# V2.net
KiCad netlist of a schematic drawn in EAGLE
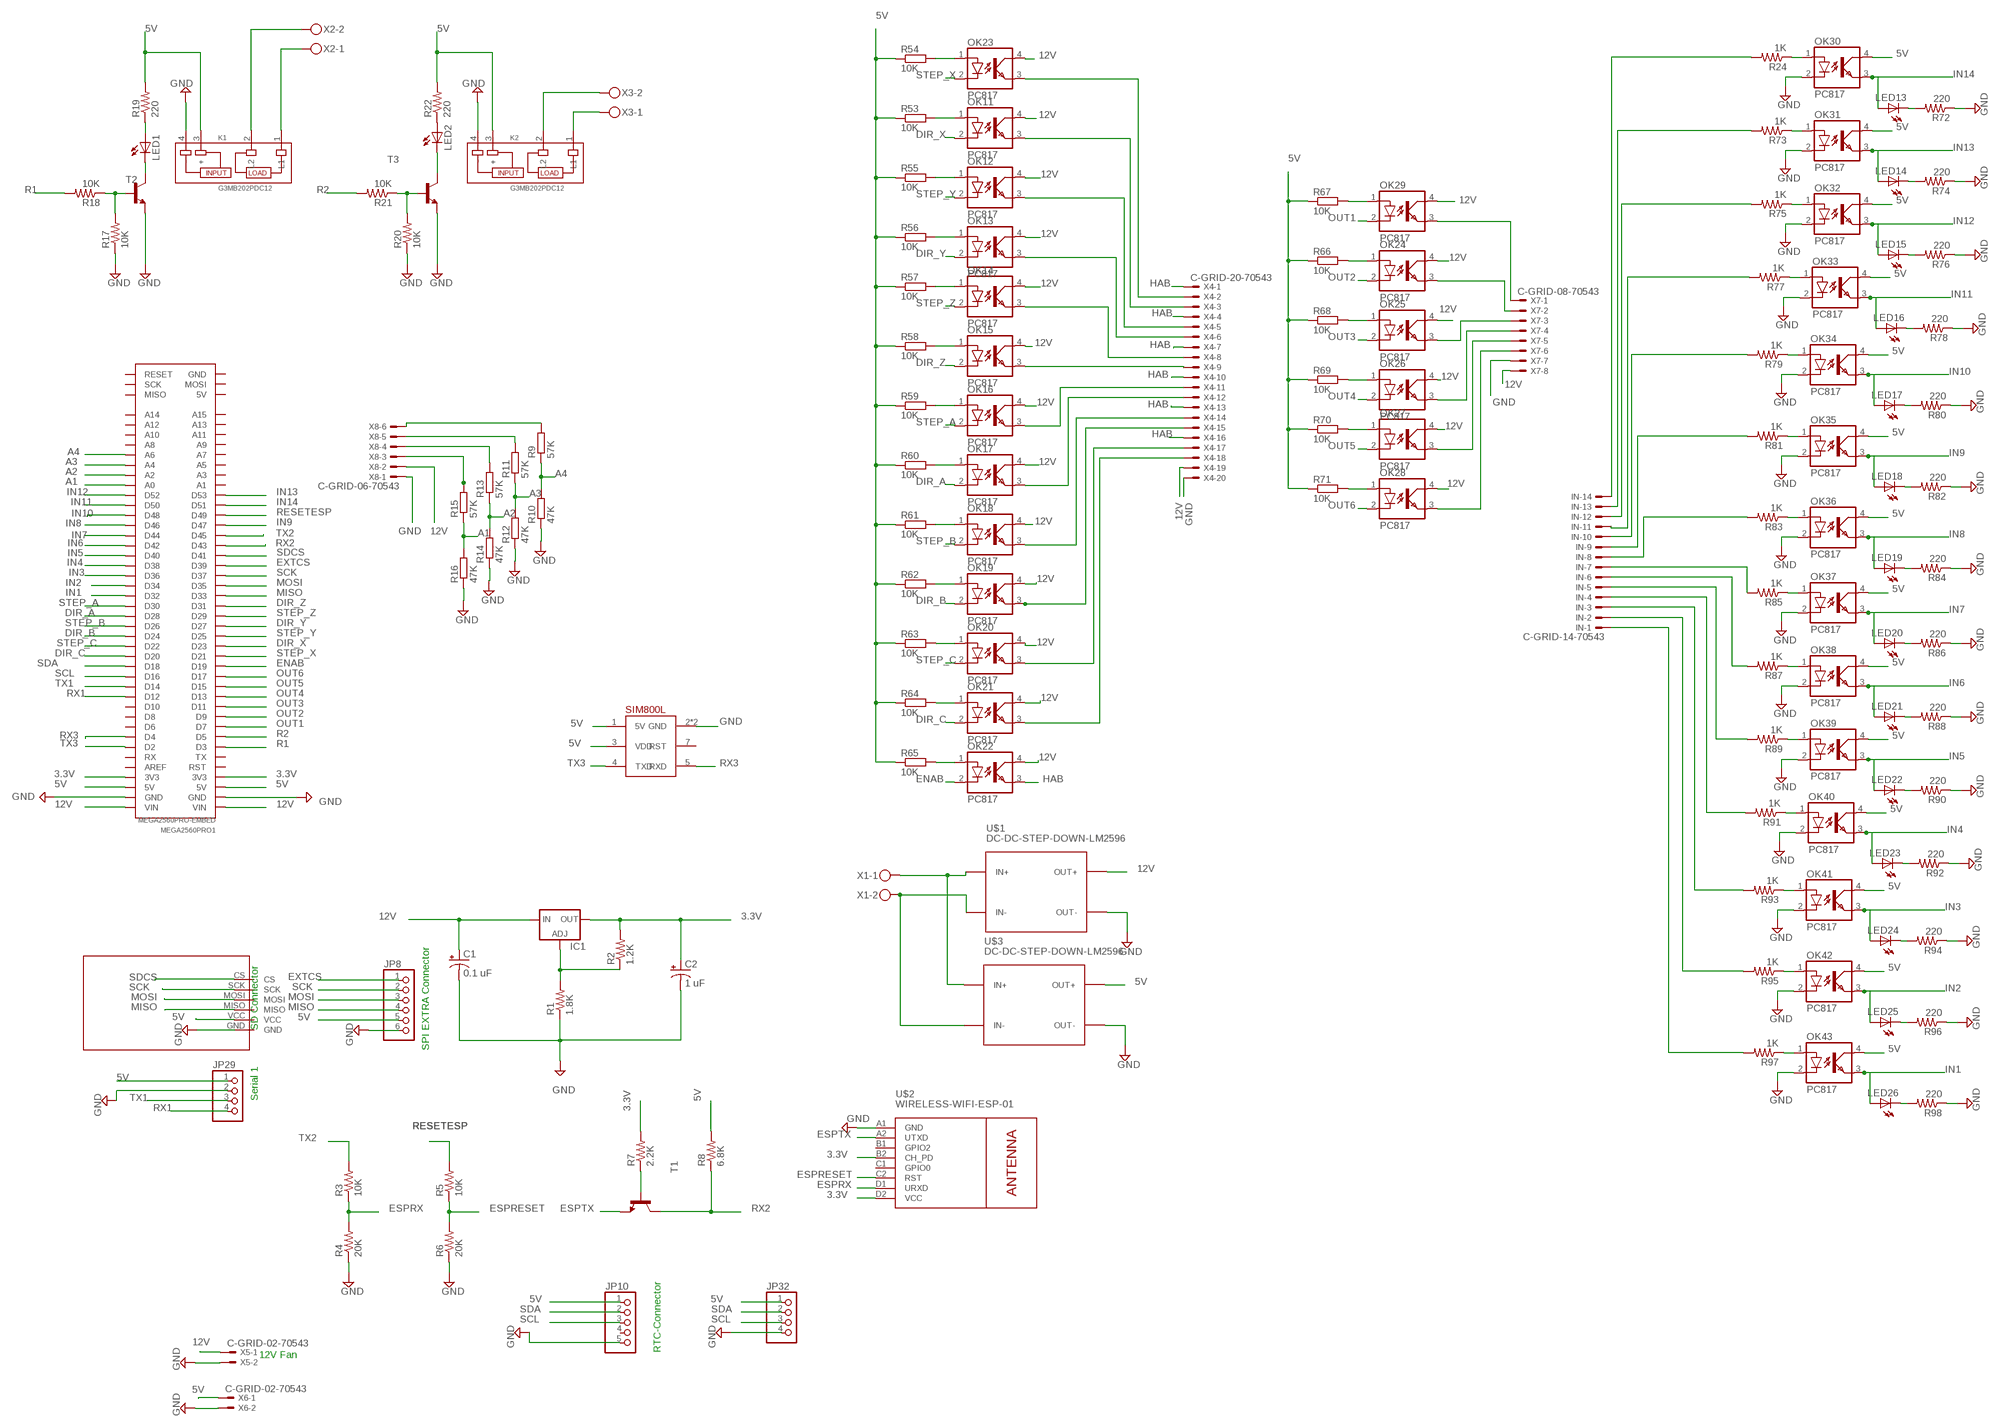
[diagram p0: schematic, sheet 1]

(export (version "E")
  (design (tool "Eeschema 10.0.6"))
  (components
    (comp (ref "C1")
      (value "0.1 uF")
      (footprint "eagle-import:E2,5-7")
      (libsource (lib "eagle-import") (part "CPOL-USE2.5-7"))
    )
    (comp (ref "C2")
      (value "1 uF")
      (footprint "eagle-import:E2,5-7")
      (libsource (lib "eagle-import") (part "CPOL-USE2.5-7"))
    )
    (comp (ref "IC1")
      (value "LM317TL")
      (footprint "eagle-import:317TL")
      (libsource (lib "eagle-import") (part "LM317TL"))
    )
    (comp (ref "IN")
      (value "C-GRID-14-70543")
      (footprint "eagle-import:70543-14")
      (fields (field (name "MF") "MOLEX"))
      (libsource (lib "eagle-import") (part "C-GRID-14-70543"))
    )
    (comp (ref "JP8")
      (value "PINHD-1X6")
      (footprint "eagle-import:1X06")
      (libsource (lib "eagle-import") (part "PINHD-1X6"))
    )
    (comp (ref "JP10")
      (value "PINHD-1X5")
      (footprint "eagle-import:1X05")
      (libsource (lib "eagle-import") (part "PINHD-1X5"))
    )
    (comp (ref "JP29")
      (value "PINHD-1X4")
      (footprint "eagle-import:1X04")
      (libsource (lib "eagle-import") (part "PINHD-1X4"))
    )
    (comp (ref "JP32")
      (value "PINHD-1X4")
      (footprint "eagle-import:1X04")
      (libsource (lib "eagle-import") (part "PINHD-1X4"))
    )
    (comp (ref "K1")
      (value "G3MB202PDC12")
      (footprint "eagle-import:RELAY_G3MB202PDC12")
      (fields (field (name "MF") "Omron Automation"))
      (libsource (lib "eagle-import") (part "G3MB202PDC12"))
    )
    (comp (ref "K2")
      (value "G3MB202PDC12")
      (footprint "eagle-import:RELAY_G3MB202PDC12")
      (fields (field (name "MF") "Omron Automation"))
      (libsource (lib "eagle-import") (part "G3MB202PDC12"))
    )
    (comp (ref "LED1")
      (value "LED3MM")
      (footprint "eagle-import:LED3MM")
      (libsource (lib "eagle-import") (part "LED3MM"))
    )
    (comp (ref "LED2")
      (value "LED3MM")
      (footprint "eagle-import:LED3MM")
      (libsource (lib "eagle-import") (part "LED3MM"))
    )
    (comp (ref "LED13")
      (value "LED3MM")
      (footprint "eagle-import:LED3MM")
      (libsource (lib "eagle-import") (part "LED3MM"))
    )
    (comp (ref "LED14")
      (value "LED3MM")
      (footprint "eagle-import:LED3MM")
      (libsource (lib "eagle-import") (part "LED3MM"))
    )
    (comp (ref "LED15")
      (value "LED3MM")
      (footprint "eagle-import:LED3MM")
      (libsource (lib "eagle-import") (part "LED3MM"))
    )
    (comp (ref "LED16")
      (value "LED3MM")
      (footprint "eagle-import:LED3MM")
      (libsource (lib "eagle-import") (part "LED3MM"))
    )
    (comp (ref "LED17")
      (value "LED3MM")
      (footprint "eagle-import:LED3MM")
      (libsource (lib "eagle-import") (part "LED3MM"))
    )
    (comp (ref "LED18")
      (value "LED3MM")
      (footprint "eagle-import:LED3MM")
      (libsource (lib "eagle-import") (part "LED3MM"))
    )
    (comp (ref "LED19")
      (value "LED3MM")
      (footprint "eagle-import:LED3MM")
      (libsource (lib "eagle-import") (part "LED3MM"))
    )
    (comp (ref "LED20")
      (value "LED3MM")
      (footprint "eagle-import:LED3MM")
      (libsource (lib "eagle-import") (part "LED3MM"))
    )
    (comp (ref "LED21")
      (value "LED3MM")
      (footprint "eagle-import:LED3MM")
      (libsource (lib "eagle-import") (part "LED3MM"))
    )
    (comp (ref "LED22")
      (value "LED3MM")
      (footprint "eagle-import:LED3MM")
      (libsource (lib "eagle-import") (part "LED3MM"))
    )
    (comp (ref "LED23")
      (value "LED3MM")
      (footprint "eagle-import:LED3MM")
      (libsource (lib "eagle-import") (part "LED3MM"))
    )
    (comp (ref "LED24")
      (value "LED3MM")
      (footprint "eagle-import:LED3MM")
      (libsource (lib "eagle-import") (part "LED3MM"))
    )
    (comp (ref "LED25")
      (value "LED3MM")
      (footprint "eagle-import:LED3MM")
      (libsource (lib "eagle-import") (part "LED3MM"))
    )
    (comp (ref "LED26")
      (value "LED3MM")
      (footprint "eagle-import:LED3MM")
      (libsource (lib "eagle-import") (part "LED3MM"))
    )
    (comp (ref "MEGA2560PRO1")
      (value "MEGA2560PRO-EMBED")
      (footprint "eagle-import:MEGA2560PRO-EMBED")
      (libsource (lib "eagle-import") (part "MEGA2560PRO-EMBED"))
    )
    (comp (ref "OK11")
      (value "PC817")
      (footprint "eagle-import:DIL04")
      (fields (field (name "MPN") "PC817X4J000F"))
      (libsource (lib "eagle-import") (part "PC817"))
    )
    (comp (ref "OK12")
      (value "PC817")
      (footprint "eagle-import:DIL04")
      (fields (field (name "MPN") "PC817X4J000F"))
      (libsource (lib "eagle-import") (part "PC817"))
    )
    (comp (ref "OK13")
      (value "PC817")
      (footprint "eagle-import:DIL04")
      (fields (field (name "MPN") "PC817X4J000F"))
      (libsource (lib "eagle-import") (part "PC817"))
    )
    (comp (ref "OK14")
      (value "PC817")
      (footprint "eagle-import:DIL04")
      (fields (field (name "MPN") "PC817X4J000F"))
      (libsource (lib "eagle-import") (part "PC817"))
    )
    (comp (ref "OK15")
      (value "PC817")
      (footprint "eagle-import:DIL04")
      (fields (field (name "MPN") "PC817X4J000F"))
      (libsource (lib "eagle-import") (part "PC817"))
    )
    (comp (ref "OK16")
      (value "PC817")
      (footprint "eagle-import:DIL04")
      (fields (field (name "MPN") "PC817X4J000F"))
      (libsource (lib "eagle-import") (part "PC817"))
    )
    (comp (ref "OK17")
      (value "PC817")
      (footprint "eagle-import:DIL04")
      (fields (field (name "MPN") "PC817X4J000F"))
      (libsource (lib "eagle-import") (part "PC817"))
    )
    (comp (ref "OK18")
      (value "PC817")
      (footprint "eagle-import:DIL04")
      (fields (field (name "MPN") "PC817X4J000F"))
      (libsource (lib "eagle-import") (part "PC817"))
    )
    (comp (ref "OK19")
      (value "PC817")
      (footprint "eagle-import:DIL04")
      (fields (field (name "MPN") "PC817X4J000F"))
      (libsource (lib "eagle-import") (part "PC817"))
    )
    (comp (ref "OK20")
      (value "PC817")
      (footprint "eagle-import:DIL04")
      (fields (field (name "MPN") "PC817X4J000F"))
      (libsource (lib "eagle-import") (part "PC817"))
    )
    (comp (ref "OK21")
      (value "PC817")
      (footprint "eagle-import:DIL04")
      (fields (field (name "MPN") "PC817X4J000F"))
      (libsource (lib "eagle-import") (part "PC817"))
    )
    (comp (ref "OK22")
      (value "PC817")
      (footprint "eagle-import:DIL04")
      (fields (field (name "MPN") "PC817X4J000F"))
      (libsource (lib "eagle-import") (part "PC817"))
    )
    (comp (ref "OK23")
      (value "PC817")
      (footprint "eagle-import:DIL04")
      (fields (field (name "MPN") "PC817X4J000F"))
      (libsource (lib "eagle-import") (part "PC817"))
    )
    (comp (ref "OK24")
      (value "PC817")
      (footprint "eagle-import:DIL04")
      (fields (field (name "MPN") "PC817X4J000F"))
      (libsource (lib "eagle-import") (part "PC817"))
    )
    (comp (ref "OK25")
      (value "PC817")
      (footprint "eagle-import:DIL04")
      (fields (field (name "MPN") "PC817X4J000F"))
      (libsource (lib "eagle-import") (part "PC817"))
    )
    (comp (ref "OK26")
      (value "PC817")
      (footprint "eagle-import:DIL04")
      (fields (field (name "MPN") "PC817X4J000F"))
      (libsource (lib "eagle-import") (part "PC817"))
    )
    (comp (ref "OK27")
      (value "PC817")
      (footprint "eagle-import:DIL04")
      (fields (field (name "MPN") "PC817X4J000F"))
      (libsource (lib "eagle-import") (part "PC817"))
    )
    (comp (ref "OK28")
      (value "PC817")
      (footprint "eagle-import:DIL04")
      (fields (field (name "MPN") "PC817X4J000F"))
      (libsource (lib "eagle-import") (part "PC817"))
    )
    (comp (ref "OK29")
      (value "PC817")
      (footprint "eagle-import:DIL04")
      (fields (field (name "MPN") "PC817X4J000F"))
      (libsource (lib "eagle-import") (part "PC817"))
    )
    (comp (ref "OK30")
      (value "PC817")
      (footprint "eagle-import:DIL04")
      (fields (field (name "MPN") "PC817X4J000F"))
      (libsource (lib "eagle-import") (part "PC817"))
    )
    (comp (ref "OK31")
      (value "PC817")
      (footprint "eagle-import:DIL04")
      (fields (field (name "MPN") "PC817X4J000F"))
      (libsource (lib "eagle-import") (part "PC817"))
    )
    (comp (ref "OK32")
      (value "PC817")
      (footprint "eagle-import:DIL04")
      (fields (field (name "MPN") "PC817X4J000F"))
      (libsource (lib "eagle-import") (part "PC817"))
    )
    (comp (ref "OK33")
      (value "PC817")
      (footprint "eagle-import:DIL04")
      (fields (field (name "MPN") "PC817X4J000F"))
      (libsource (lib "eagle-import") (part "PC817"))
    )
    (comp (ref "OK34")
      (value "PC817")
      (footprint "eagle-import:DIL04")
      (fields (field (name "MPN") "PC817X4J000F"))
      (libsource (lib "eagle-import") (part "PC817"))
    )
    (comp (ref "OK35")
      (value "PC817")
      (footprint "eagle-import:DIL04")
      (fields (field (name "MPN") "PC817X4J000F"))
      (libsource (lib "eagle-import") (part "PC817"))
    )
    (comp (ref "OK36")
      (value "PC817")
      (footprint "eagle-import:DIL04")
      (fields (field (name "MPN") "PC817X4J000F"))
      (libsource (lib "eagle-import") (part "PC817"))
    )
    (comp (ref "OK37")
      (value "PC817")
      (footprint "eagle-import:DIL04")
      (fields (field (name "MPN") "PC817X4J000F"))
      (libsource (lib "eagle-import") (part "PC817"))
    )
    (comp (ref "OK38")
      (value "PC817")
      (footprint "eagle-import:DIL04")
      (fields (field (name "MPN") "PC817X4J000F"))
      (libsource (lib "eagle-import") (part "PC817"))
    )
    (comp (ref "OK39")
      (value "PC817")
      (footprint "eagle-import:DIL04")
      (fields (field (name "MPN") "PC817X4J000F"))
      (libsource (lib "eagle-import") (part "PC817"))
    )
    (comp (ref "OK40")
      (value "PC817")
      (footprint "eagle-import:DIL04")
      (fields (field (name "MPN") "PC817X4J000F"))
      (libsource (lib "eagle-import") (part "PC817"))
    )
    (comp (ref "OK41")
      (value "PC817")
      (footprint "eagle-import:DIL04")
      (fields (field (name "MPN") "PC817X4J000F"))
      (libsource (lib "eagle-import") (part "PC817"))
    )
    (comp (ref "OK42")
      (value "PC817")
      (footprint "eagle-import:DIL04")
      (fields (field (name "MPN") "PC817X4J000F"))
      (libsource (lib "eagle-import") (part "PC817"))
    )
    (comp (ref "OK43")
      (value "PC817")
      (footprint "eagle-import:DIL04")
      (fields (field (name "MPN") "PC817X4J000F"))
      (libsource (lib "eagle-import") (part "PC817"))
    )
    (comp (ref "R1")
      (value "1.8K")
      (footprint "eagle-import:0207_10")
      (libsource (lib "eagle-import") (part "R-US_0207/10"))
    )
    (comp (ref "R2")
      (value "1.2K")
      (footprint "eagle-import:0207_10")
      (libsource (lib "eagle-import") (part "R-US_0207/10"))
    )
    (comp (ref "R3")
      (value "10K")
      (footprint "eagle-import:0207_10")
      (libsource (lib "eagle-import") (part "R-US_0207/10"))
    )
    (comp (ref "R4")
      (value "20K")
      (footprint "eagle-import:0207_10")
      (libsource (lib "eagle-import") (part "R-US_0207/10"))
    )
    (comp (ref "R5")
      (value "10K")
      (footprint "eagle-import:0207_10")
      (libsource (lib "eagle-import") (part "R-US_0207/10"))
    )
    (comp (ref "R6")
      (value "20K")
      (footprint "eagle-import:0207_10")
      (libsource (lib "eagle-import") (part "R-US_0207/10"))
    )
    (comp (ref "R7")
      (value "2.2K")
      (footprint "eagle-import:0207_10")
      (libsource (lib "eagle-import") (part "R-US_0207/10"))
    )
    (comp (ref "R8")
      (value "6.8K")
      (footprint "eagle-import:0207_10")
      (libsource (lib "eagle-import") (part "R-US_0207/10"))
    )
    (comp (ref "R9")
      (value "57K")
      (footprint "eagle-import:0207_7")
      (libsource (lib "eagle-import") (part "R-EU_0207/7"))
    )
    (comp (ref "R10")
      (value "47K")
      (footprint "eagle-import:0207_7")
      (libsource (lib "eagle-import") (part "R-EU_0207/7"))
    )
    (comp (ref "R11")
      (value "57K")
      (footprint "eagle-import:0207_7")
      (libsource (lib "eagle-import") (part "R-EU_0207/7"))
    )
    (comp (ref "R12")
      (value "47K")
      (footprint "eagle-import:0207_7")
      (libsource (lib "eagle-import") (part "R-EU_0207/7"))
    )
    (comp (ref "R13")
      (value "57K")
      (footprint "eagle-import:0207_7")
      (libsource (lib "eagle-import") (part "R-EU_0207/7"))
    )
    (comp (ref "R14")
      (value "47K")
      (footprint "eagle-import:0207_7")
      (libsource (lib "eagle-import") (part "R-EU_0207/7"))
    )
    (comp (ref "R15")
      (value "57K")
      (footprint "eagle-import:0207_7")
      (libsource (lib "eagle-import") (part "R-EU_0207/7"))
    )
    (comp (ref "R16")
      (value "47K")
      (footprint "eagle-import:0207_7")
      (libsource (lib "eagle-import") (part "R-EU_0207/7"))
    )
    (comp (ref "R17")
      (value "10K")
      (footprint "eagle-import:0207_10")
      (libsource (lib "eagle-import") (part "R-US_0207/10"))
    )
    (comp (ref "R18")
      (value "10K")
      (footprint "eagle-import:0207_10")
      (libsource (lib "eagle-import") (part "R-US_0207/10"))
    )
    (comp (ref "R19")
      (value "220")
      (footprint "eagle-import:0207_10")
      (libsource (lib "eagle-import") (part "R-US_0207/10"))
    )
    (comp (ref "R20")
      (value "10K")
      (footprint "eagle-import:0207_10")
      (libsource (lib "eagle-import") (part "R-US_0207/10"))
    )
    (comp (ref "R21")
      (value "10K")
      (footprint "eagle-import:0207_10")
      (libsource (lib "eagle-import") (part "R-US_0207/10"))
    )
    (comp (ref "R22")
      (value "220")
      (footprint "eagle-import:0207_10")
      (libsource (lib "eagle-import") (part "R-US_0207/10"))
    )
    (comp (ref "R24")
      (value "1K")
      (footprint "eagle-import:0207_10")
      (libsource (lib "eagle-import") (part "R-US_0207/10"))
    )
    (comp (ref "R53")
      (value "10K")
      (footprint "eagle-import:0207_7")
      (libsource (lib "eagle-import") (part "R-EU_0207/7"))
    )
    (comp (ref "R54")
      (value "10K")
      (footprint "eagle-import:0207_7")
      (libsource (lib "eagle-import") (part "R-EU_0207/7"))
    )
    (comp (ref "R55")
      (value "10K")
      (footprint "eagle-import:0207_7")
      (libsource (lib "eagle-import") (part "R-EU_0207/7"))
    )
    (comp (ref "R56")
      (value "10K")
      (footprint "eagle-import:0207_7")
      (libsource (lib "eagle-import") (part "R-EU_0207/7"))
    )
    (comp (ref "R57")
      (value "10K")
      (footprint "eagle-import:0207_7")
      (libsource (lib "eagle-import") (part "R-EU_0207/7"))
    )
    (comp (ref "R58")
      (value "10K")
      (footprint "eagle-import:0207_7")
      (libsource (lib "eagle-import") (part "R-EU_0207/7"))
    )
    (comp (ref "R59")
      (value "10K")
      (footprint "eagle-import:0207_7")
      (libsource (lib "eagle-import") (part "R-EU_0207/7"))
    )
    (comp (ref "R60")
      (value "10K")
      (footprint "eagle-import:0207_7")
      (libsource (lib "eagle-import") (part "R-EU_0207/7"))
    )
    (comp (ref "R61")
      (value "10K")
      (footprint "eagle-import:0207_7")
      (libsource (lib "eagle-import") (part "R-EU_0207/7"))
    )
    (comp (ref "R62")
      (value "10K")
      (footprint "eagle-import:0207_7")
      (libsource (lib "eagle-import") (part "R-EU_0207/7"))
    )
    (comp (ref "R63")
      (value "10K")
      (footprint "eagle-import:0207_7")
      (libsource (lib "eagle-import") (part "R-EU_0207/7"))
    )
    (comp (ref "R64")
      (value "10K")
      (footprint "eagle-import:0207_7")
      (libsource (lib "eagle-import") (part "R-EU_0207/7"))
    )
    (comp (ref "R65")
      (value "10K")
      (footprint "eagle-import:0207_7")
      (libsource (lib "eagle-import") (part "R-EU_0207/7"))
    )
    (comp (ref "R66")
      (value "10K")
      (footprint "eagle-import:0207_7")
      (libsource (lib "eagle-import") (part "R-EU_0207/7"))
    )
    (comp (ref "R67")
      (value "10K")
      (footprint "eagle-import:0207_7")
      (libsource (lib "eagle-import") (part "R-EU_0207/7"))
    )
    (comp (ref "R68")
      (value "10K")
      (footprint "eagle-import:0207_7")
      (libsource (lib "eagle-import") (part "R-EU_0207/7"))
    )
    (comp (ref "R69")
      (value "10K")
      (footprint "eagle-import:0207_7")
      (libsource (lib "eagle-import") (part "R-EU_0207/7"))
    )
    (comp (ref "R70")
      (value "10K")
      (footprint "eagle-import:0207_7")
      (libsource (lib "eagle-import") (part "R-EU_0207/7"))
    )
    (comp (ref "R71")
      (value "10K")
      (footprint "eagle-import:0207_7")
      (libsource (lib "eagle-import") (part "R-EU_0207/7"))
    )
    (comp (ref "R72")
      (value "220")
      (footprint "eagle-import:0207_10")
      (libsource (lib "eagle-import") (part "R-US_0207/10"))
    )
    (comp (ref "R73")
      (value "1K")
      (footprint "eagle-import:0207_10")
      (libsource (lib "eagle-import") (part "R-US_0207/10"))
    )
    (comp (ref "R74")
      (value "220")
      (footprint "eagle-import:0207_10")
      (libsource (lib "eagle-import") (part "R-US_0207/10"))
    )
    (comp (ref "R75")
      (value "1K")
      (footprint "eagle-import:0207_10")
      (libsource (lib "eagle-import") (part "R-US_0207/10"))
    )
    (comp (ref "R76")
      (value "220")
      (footprint "eagle-import:0207_10")
      (libsource (lib "eagle-import") (part "R-US_0207/10"))
    )
    (comp (ref "R77")
      (value "1K")
      (footprint "eagle-import:0207_10")
      (libsource (lib "eagle-import") (part "R-US_0207/10"))
    )
    (comp (ref "R78")
      (value "220")
      (footprint "eagle-import:0207_10")
      (libsource (lib "eagle-import") (part "R-US_0207/10"))
    )
    (comp (ref "R79")
      (value "1K")
      (footprint "eagle-import:0207_10")
      (libsource (lib "eagle-import") (part "R-US_0207/10"))
    )
    (comp (ref "R80")
      (value "220")
      (footprint "eagle-import:0207_10")
      (libsource (lib "eagle-import") (part "R-US_0207/10"))
    )
    (comp (ref "R81")
      (value "1K")
      (footprint "eagle-import:0207_10")
      (libsource (lib "eagle-import") (part "R-US_0207/10"))
    )
    (comp (ref "R82")
      (value "220")
      (footprint "eagle-import:0207_10")
      (libsource (lib "eagle-import") (part "R-US_0207/10"))
    )
    (comp (ref "R83")
      (value "1K")
      (footprint "eagle-import:0207_10")
      (libsource (lib "eagle-import") (part "R-US_0207/10"))
    )
    (comp (ref "R84")
      (value "220")
      (footprint "eagle-import:0207_10")
      (libsource (lib "eagle-import") (part "R-US_0207/10"))
    )
    (comp (ref "R85")
      (value "1K")
      (footprint "eagle-import:0207_10")
      (libsource (lib "eagle-import") (part "R-US_0207/10"))
    )
    (comp (ref "R86")
      (value "220")
      (footprint "eagle-import:0207_10")
      (libsource (lib "eagle-import") (part "R-US_0207/10"))
    )
    (comp (ref "R87")
      (value "1K")
      (footprint "eagle-import:0207_10")
      (libsource (lib "eagle-import") (part "R-US_0207/10"))
    )
    (comp (ref "R88")
      (value "220")
      (footprint "eagle-import:0207_10")
      (libsource (lib "eagle-import") (part "R-US_0207/10"))
    )
    (comp (ref "R89")
      (value "1K")
      (footprint "eagle-import:0207_10")
      (libsource (lib "eagle-import") (part "R-US_0207/10"))
    )
    (comp (ref "R90")
      (value "220")
      (footprint "eagle-import:0207_10")
      (libsource (lib "eagle-import") (part "R-US_0207/10"))
    )
    (comp (ref "R91")
      (value "1K")
      (footprint "eagle-import:0207_10")
      (libsource (lib "eagle-import") (part "R-US_0207/10"))
    )
    (comp (ref "R92")
      (value "220")
      (footprint "eagle-import:0207_10")
      (libsource (lib "eagle-import") (part "R-US_0207/10"))
    )
    (comp (ref "R93")
      (value "1K")
      (footprint "eagle-import:0207_10")
      (libsource (lib "eagle-import") (part "R-US_0207/10"))
    )
    (comp (ref "R94")
      (value "220")
      (footprint "eagle-import:0207_10")
      (libsource (lib "eagle-import") (part "R-US_0207/10"))
    )
    (comp (ref "R95")
      (value "1K")
      (footprint "eagle-import:0207_10")
      (libsource (lib "eagle-import") (part "R-US_0207/10"))
    )
    (comp (ref "R96")
      (value "220")
      (footprint "eagle-import:0207_10")
      (libsource (lib "eagle-import") (part "R-US_0207/10"))
    )
    (comp (ref "R97")
      (value "1K")
      (footprint "eagle-import:0207_10")
      (libsource (lib "eagle-import") (part "R-US_0207/10"))
    )
    (comp (ref "R98")
      (value "220")
      (footprint "eagle-import:0207_10")
      (libsource (lib "eagle-import") (part "R-US_0207/10"))
    )
    (comp (ref "T1")
      (value "29-NPN-TO92-EBC")
      (footprint "eagle-import:TO92-EBC")
      (libsource (lib "eagle-import") (part "-NPN-TO92-EBC29"))
    )
    (comp (ref "T2")
      (value "29-NPN-TO92-EBC")
      (footprint "eagle-import:TO92-EBC")
      (libsource (lib "eagle-import") (part "-NPN-TO92-EBC29"))
    )
    (comp (ref "T3")
      (value "29-NPN-TO92-EBC")
      (footprint "eagle-import:TO92-EBC")
      (libsource (lib "eagle-import") (part "-NPN-TO92-EBC29"))
    )
    (comp (ref "U$1")
      (value "DC-DC-STEP-DOWN-LM2596")
      (footprint "eagle-import:DC-DC-STEP-DOWN-LM2596")
      (libsource (lib "eagle-import") (part "DC-DC-STEP-DOWN-LM2596"))
    )
    (comp (ref "U$2")
      (value "WIRELESS-WIFI-ESP-01")
      (footprint "eagle-import:WIRELESS-WIFI-ESP-01")
      (libsource (lib "eagle-import") (part "WIRELESS-WIFI-ESP-01"))
    )
    (comp (ref "U$3")
      (value "DC-DC-STEP-DOWN-LM2596")
      (footprint "eagle-import:DC-DC-STEP-DOWN-LM2596")
      (libsource (lib "eagle-import") (part "DC-DC-STEP-DOWN-LM2596"))
    )
    (comp (ref "U$4")
      (value "SIM800L")
      (footprint "eagle-import:SIP")
      (libsource (lib "eagle-import") (part "SIM800L"))
    )
    (comp (ref "U$9")
      (value "MODULO_SD")
      (footprint "eagle-import:MODULO_SD")
      (libsource (lib "eagle-import") (part "MODULO_SD"))
    )
    (comp (ref "X1")
      (value "MKDSN1,5/2-5,08")
      (footprint "eagle-import:MKDSN1,5_2-5,08")
      (libsource (lib "eagle-import") (part "MKDSN1,5/2-5,08"))
    )
    (comp (ref "X2")
      (value "MKDSN1,5/2-5,08")
      (footprint "eagle-import:MKDSN1,5_2-5,08")
      (libsource (lib "eagle-import") (part "MKDSN1,5/2-5,08"))
    )
    (comp (ref "X3")
      (value "MKDSN1,5/2-5,08")
      (footprint "eagle-import:MKDSN1,5_2-5,08")
      (libsource (lib "eagle-import") (part "MKDSN1,5/2-5,08"))
    )
    (comp (ref "X4")
      (value "C-GRID-20-70543")
      (footprint "eagle-import:70543-20")
      (fields (field (name "MF") "MOLEX"))
      (libsource (lib "eagle-import") (part "C-GRID-20-70543"))
    )
    (comp (ref "X5")
      (value "C-GRID-02-70543")
      (footprint "eagle-import:70543-02")
      (fields (field (name "MF") "MOLEX"))
      (libsource (lib "eagle-import") (part "C-GRID-02-70543"))
    )
    (comp (ref "X6")
      (value "C-GRID-02-70543")
      (footprint "eagle-import:70543-02")
      (fields (field (name "MF") "MOLEX"))
      (libsource (lib "eagle-import") (part "C-GRID-02-70543"))
    )
    (comp (ref "X7")
      (value "C-GRID-08-70543")
      (footprint "eagle-import:70543-08")
      (fields (field (name "MF") "MOLEX"))
      (libsource (lib "eagle-import") (part "C-GRID-08-70543"))
    )
    (comp (ref "X8")
      (value "C-GRID-06-70543")
      (footprint "eagle-import:70543-06")
      (fields (field (name "MF") "MOLEX"))
      (libsource (lib "eagle-import") (part "C-GRID-06-70543"))
    )
  )
  (nets
    (net (code "1") (name "/3.3V") (class "Default")
      (node (ref "C2") (pin "+") (pinfunction "+_+") (pintype "passive"))
      (node (ref "IC1") (pin "2") (pinfunction "OUT_2") (pintype "passive"))
      (node (ref "MEGA2560PRO1") (pin "3V3@1") (pinfunction "3V3_3V3@1") (pintype "bidirectional"))
      (node (ref "MEGA2560PRO1") (pin "3V3@2") (pinfunction "3V3_3V3@2") (pintype "bidirectional"))
      (node (ref "R2") (pin "2") (pinfunction "2_2") (pintype "passive"))
      (node (ref "R7") (pin "2") (pinfunction "2_2") (pintype "passive"))
      (node (ref "U$2") (pin "B2") (pinfunction "CH_PD_B2") (pintype "bidirectional"))
      (node (ref "U$2") (pin "D2") (pinfunction "VCC_D2") (pintype "power_in"))
    )
    (net (code "2") (name "/5V") (class "Default")
      (node (ref "JP10") (pin "1") (pinfunction "1_1") (pintype "passive"))
      (node (ref "JP29") (pin "1") (pinfunction "1_1") (pintype "passive"))
      (node (ref "JP32") (pin "1") (pinfunction "1_1") (pintype "passive"))
      (node (ref "JP8") (pin "5") (pinfunction "5_5") (pintype "passive"))
      (node (ref "K1") (pin "3") (pinfunction "+_3") (pintype "power_in"))
      (node (ref "K2") (pin "3") (pinfunction "+_3") (pintype "power_in"))
      (node (ref "MEGA2560PRO1") (pin "5V@1") (pinfunction "5V_5V@1") (pintype "bidirectional"))
      (node (ref "MEGA2560PRO1") (pin "5V@2") (pinfunction "5V_5V@2") (pintype "bidirectional"))
      (node (ref "OK30") (pin "4") (pinfunction "COL_4") (pintype "passive"))
      (node (ref "OK31") (pin "4") (pinfunction "COL_4") (pintype "passive"))
      (node (ref "OK32") (pin "4") (pinfunction "COL_4") (pintype "passive"))
      (node (ref "OK33") (pin "4") (pinfunction "COL_4") (pintype "passive"))
      (node (ref "OK34") (pin "4") (pinfunction "COL_4") (pintype "passive"))
      (node (ref "OK35") (pin "4") (pinfunction "COL_4") (pintype "passive"))
      (node (ref "OK36") (pin "4") (pinfunction "COL_4") (pintype "passive"))
      (node (ref "OK37") (pin "4") (pinfunction "COL_4") (pintype "passive"))
      (node (ref "OK38") (pin "4") (pinfunction "COL_4") (pintype "passive"))
      (node (ref "OK39") (pin "4") (pinfunction "COL_4") (pintype "passive"))
      (node (ref "OK40") (pin "4") (pinfunction "COL_4") (pintype "passive"))
      (node (ref "OK41") (pin "4") (pinfunction "COL_4") (pintype "passive"))
      (node (ref "OK42") (pin "4") (pinfunction "COL_4") (pintype "passive"))
      (node (ref "OK43") (pin "4") (pinfunction "COL_4") (pintype "passive"))
      (node (ref "R19") (pin "2") (pinfunction "2_2") (pintype "passive"))
      (node (ref "R22") (pin "2") (pinfunction "2_2") (pintype "passive"))
      (node (ref "R53") (pin "1") (pinfunction "1_1") (pintype "passive"))
      (node (ref "R54") (pin "1") (pinfunction "1_1") (pintype "passive"))
      (node (ref "R55") (pin "1") (pinfunction "1_1") (pintype "passive"))
      (node (ref "R56") (pin "1") (pinfunction "1_1") (pintype "passive"))
      (node (ref "R57") (pin "1") (pinfunction "1_1") (pintype "passive"))
      (node (ref "R58") (pin "1") (pinfunction "1_1") (pintype "passive"))
      (node (ref "R59") (pin "1") (pinfunction "1_1") (pintype "passive"))
      (node (ref "R60") (pin "1") (pinfunction "1_1") (pintype "passive"))
      (node (ref "R61") (pin "1") (pinfunction "1_1") (pintype "passive"))
      (node (ref "R62") (pin "1") (pinfunction "1_1") (pintype "passive"))
      (node (ref "R63") (pin "1") (pinfunction "1_1") (pintype "passive"))
      (node (ref "R64") (pin "1") (pinfunction "1_1") (pintype "passive"))
      (node (ref "R65") (pin "1") (pinfunction "1_1") (pintype "passive"))
      (node (ref "R66") (pin "1") (pinfunction "1_1") (pintype "passive"))
      (node (ref "R67") (pin "1") (pinfunction "1_1") (pintype "passive"))
      (node (ref "R68") (pin "1") (pinfunction "1_1") (pintype "passive"))
      (node (ref "R69") (pin "1") (pinfunction "1_1") (pintype "passive"))
      (node (ref "R70") (pin "1") (pinfunction "1_1") (pintype "passive"))
      (node (ref "R71") (pin "1") (pinfunction "1_1") (pintype "passive"))
      (node (ref "R8") (pin "2") (pinfunction "2_2") (pintype "passive"))
      (node (ref "U$3") (pin "OUT+") (pinfunction "OUT+_OUT+") (pintype "bidirectional"))
      (node (ref "U$4") (pin "1") (pinfunction "5V_1") (pintype "bidirectional"))
      (node (ref "U$4") (pin "3") (pinfunction "VDD_3") (pintype "bidirectional"))
      (node (ref "U$9") (pin "VCC") (pinfunction "VCC_VCC") (pintype "bidirectional"))
      (node (ref "X6") (pin "1") (pinfunction "S_1") (pintype "passive"))
    )
    (net (code "3") (name "/12V") (class "Default")
      (node (ref "C1") (pin "+") (pinfunction "+_+") (pintype "passive"))
      (node (ref "IC1") (pin "3") (pinfunction "IN_3") (pintype "input"))
      (node (ref "MEGA2560PRO1") (pin "VIN@1") (pinfunction "VIN_VIN@1") (pintype "bidirectional"))
      (node (ref "MEGA2560PRO1") (pin "VIN@2") (pinfunction "VIN_VIN@2") (pintype "bidirectional"))
      (node (ref "OK11") (pin "4") (pinfunction "COL_4") (pintype "passive"))
      (node (ref "OK12") (pin "4") (pinfunction "COL_4") (pintype "passive"))
      (node (ref "OK13") (pin "4") (pinfunction "COL_4") (pintype "passive"))
      (node (ref "OK14") (pin "4") (pinfunction "COL_4") (pintype "passive"))
      (node (ref "OK15") (pin "4") (pinfunction "COL_4") (pintype "passive"))
      (node (ref "OK16") (pin "4") (pinfunction "COL_4") (pintype "passive"))
      (node (ref "OK17") (pin "4") (pinfunction "COL_4") (pintype "passive"))
      (node (ref "OK18") (pin "4") (pinfunction "COL_4") (pintype "passive"))
      (node (ref "OK19") (pin "4") (pinfunction "COL_4") (pintype "passive"))
      (node (ref "OK20") (pin "4") (pinfunction "COL_4") (pintype "passive"))
      (node (ref "OK21") (pin "4") (pinfunction "COL_4") (pintype "passive"))
      (node (ref "OK22") (pin "4") (pinfunction "COL_4") (pintype "passive"))
      (node (ref "OK23") (pin "4") (pinfunction "COL_4") (pintype "passive"))
      (node (ref "OK24") (pin "4") (pinfunction "COL_4") (pintype "passive"))
      (node (ref "OK25") (pin "4") (pinfunction "COL_4") (pintype "passive"))
      (node (ref "OK26") (pin "4") (pinfunction "COL_4") (pintype "passive"))
      (node (ref "OK27") (pin "4") (pinfunction "COL_4") (pintype "passive"))
      (node (ref "OK28") (pin "4") (pinfunction "COL_4") (pintype "passive"))
      (node (ref "OK29") (pin "4") (pinfunction "COL_4") (pintype "passive"))
      (node (ref "U$1") (pin "OUT+") (pinfunction "OUT+_OUT+") (pintype "bidirectional"))
      (node (ref "X4") (pin "19") (pinfunction "S_19") (pintype "passive"))
      (node (ref "X5") (pin "1") (pinfunction "S_1") (pintype "passive"))
      (node (ref "X7") (pin "8") (pinfunction "S_8") (pintype "passive"))
      (node (ref "X8") (pin "2") (pinfunction "S_2") (pintype "passive"))
    )
    (net (code "4") (name "/A1") (class "Default")
      (node (ref "MEGA2560PRO1") (pin "A0") (pinfunction "A0_A0") (pintype "bidirectional"))
      (node (ref "R15") (pin "1") (pinfunction "1_1") (pintype "passive"))
      (node (ref "R16") (pin "2") (pinfunction "2_2") (pintype "passive"))
    )
    (net (code "5") (name "/A2") (class "Default")
      (node (ref "MEGA2560PRO1") (pin "A2") (pinfunction "A2_A2") (pintype "bidirectional"))
      (node (ref "R13") (pin "1") (pinfunction "1_1") (pintype "passive"))
      (node (ref "R14") (pin "2") (pinfunction "2_2") (pintype "passive"))
    )
    (net (code "6") (name "/A3") (class "Default")
      (node (ref "MEGA2560PRO1") (pin "A4") (pinfunction "A4_A4") (pintype "bidirectional"))
      (node (ref "R11") (pin "1") (pinfunction "1_1") (pintype "passive"))
      (node (ref "R12") (pin "2") (pinfunction "2_2") (pintype "passive"))
    )
    (net (code "7") (name "/A4") (class "Default")
      (node (ref "MEGA2560PRO1") (pin "A6") (pinfunction "A6_A6") (pintype "bidirectional"))
      (node (ref "R10") (pin "2") (pinfunction "2_2") (pintype "passive"))
      (node (ref "R9") (pin "1") (pinfunction "1_1") (pintype "passive"))
    )
    (net (code "8") (name "/DIR_A") (class "Default")
      (node (ref "MEGA2560PRO1") (pin "D28") (pinfunction "D28_D28") (pintype "bidirectional"))
      (node (ref "OK17") (pin "2") (pinfunction "C_2") (pintype "passive"))
    )
    (net (code "9") (name "/DIR_B") (class "Default")
      (node (ref "MEGA2560PRO1") (pin "D24") (pinfunction "D24_D24") (pintype "bidirectional"))
      (node (ref "OK19") (pin "2") (pinfunction "C_2") (pintype "passive"))
    )
    (net (code "10") (name "/DIR_C") (class "Default")
      (node (ref "MEGA2560PRO1") (pin "D20") (pinfunction "D20_D20") (pintype "bidirectional"))
      (node (ref "OK21") (pin "2") (pinfunction "C_2") (pintype "passive"))
    )
    (net (code "11") (name "/DIR_X") (class "Default")
      (node (ref "MEGA2560PRO1") (pin "D23") (pinfunction "D23_D23") (pintype "bidirectional"))
      (node (ref "OK11") (pin "2") (pinfunction "C_2") (pintype "passive"))
    )
    (net (code "12") (name "/DIR_Y") (class "Default")
      (node (ref "MEGA2560PRO1") (pin "D27") (pinfunction "D27_D27") (pintype "bidirectional"))
      (node (ref "OK13") (pin "2") (pinfunction "C_2") (pintype "passive"))
    )
    (net (code "13") (name "/DIR_Z") (class "Default")
      (node (ref "MEGA2560PRO1") (pin "D31") (pinfunction "D31_D31") (pintype "bidirectional"))
      (node (ref "OK15") (pin "2") (pinfunction "C_2") (pintype "passive"))
    )
    (net (code "14") (name "/ENAB") (class "Default")
      (node (ref "MEGA2560PRO1") (pin "D19") (pinfunction "D19_D19") (pintype "bidirectional"))
      (node (ref "OK22") (pin "2") (pinfunction "C_2") (pintype "passive"))
    )
    (net (code "15") (name "/ESPRESET") (class "Default")
      (node (ref "R5") (pin "1") (pinfunction "1_1") (pintype "passive"))
      (node (ref "R6") (pin "2") (pinfunction "2_2") (pintype "passive"))
      (node (ref "U$2") (pin "C2") (pinfunction "RST_C2") (pintype "bidirectional"))
    )
    (net (code "16") (name "/ESPRX") (class "Default")
      (node (ref "R3") (pin "1") (pinfunction "1_1") (pintype "passive"))
      (node (ref "R4") (pin "2") (pinfunction "2_2") (pintype "passive"))
      (node (ref "U$2") (pin "D1") (pinfunction "URXD_D1") (pintype "bidirectional"))
    )
    (net (code "17") (name "/ESPTX") (class "Default")
      (node (ref "T1") (pin "E") (pinfunction "E_E") (pintype "passive"))
      (node (ref "U$2") (pin "A2") (pinfunction "UTXD_A2") (pintype "bidirectional"))
    )
    (net (code "18") (name "/EXTCS") (class "Default")
      (node (ref "JP8") (pin "1") (pinfunction "1_1") (pintype "passive"))
      (node (ref "MEGA2560PRO1") (pin "D39") (pinfunction "D39_D39") (pintype "bidirectional"))
    )
    (net (code "19") (name "/HAB") (class "Default")
      (node (ref "OK22") (pin "3") (pinfunction "EMIT_3") (pintype "passive"))
      (node (ref "X4") (pin "1") (pinfunction "S_1") (pintype "passive"))
      (node (ref "X4") (pin "10") (pinfunction "S_10") (pintype "passive"))
      (node (ref "X4") (pin "13") (pinfunction "S_13") (pintype "passive"))
      (node (ref "X4") (pin "16") (pinfunction "S_16") (pintype "passive"))
      (node (ref "X4") (pin "4") (pinfunction "S_4") (pintype "passive"))
      (node (ref "X4") (pin "7") (pinfunction "S_7") (pintype "passive"))
    )
    (net (code "20") (name "/IN1") (class "Default")
      (node (ref "LED26") (pin "A") (pinfunction "A_A") (pintype "passive"))
      (node (ref "MEGA2560PRO1") (pin "D32") (pinfunction "D32_D32") (pintype "bidirectional"))
      (node (ref "OK43") (pin "3") (pinfunction "EMIT_3") (pintype "passive"))
    )
    (net (code "21") (name "/IN2") (class "Default")
      (node (ref "LED25") (pin "A") (pinfunction "A_A") (pintype "passive"))
      (node (ref "MEGA2560PRO1") (pin "D34") (pinfunction "D34_D34") (pintype "bidirectional"))
      (node (ref "OK42") (pin "3") (pinfunction "EMIT_3") (pintype "passive"))
    )
    (net (code "22") (name "/IN3") (class "Default")
      (node (ref "LED24") (pin "A") (pinfunction "A_A") (pintype "passive"))
      (node (ref "MEGA2560PRO1") (pin "D36") (pinfunction "D36_D36") (pintype "bidirectional"))
      (node (ref "OK41") (pin "3") (pinfunction "EMIT_3") (pintype "passive"))
    )
    (net (code "23") (name "/IN4") (class "Default")
      (node (ref "LED23") (pin "A") (pinfunction "A_A") (pintype "passive"))
      (node (ref "MEGA2560PRO1") (pin "D38") (pinfunction "D38_D38") (pintype "bidirectional"))
      (node (ref "OK40") (pin "3") (pinfunction "EMIT_3") (pintype "passive"))
    )
    (net (code "24") (name "/IN5") (class "Default")
      (node (ref "LED22") (pin "A") (pinfunction "A_A") (pintype "passive"))
      (node (ref "MEGA2560PRO1") (pin "D40") (pinfunction "D40_D40") (pintype "bidirectional"))
      (node (ref "OK39") (pin "3") (pinfunction "EMIT_3") (pintype "passive"))
    )
    (net (code "25") (name "/IN6") (class "Default")
      (node (ref "LED21") (pin "A") (pinfunction "A_A") (pintype "passive"))
      (node (ref "MEGA2560PRO1") (pin "D42") (pinfunction "D42_D42") (pintype "bidirectional"))
      (node (ref "OK38") (pin "3") (pinfunction "EMIT_3") (pintype "passive"))
    )
    (net (code "26") (name "/IN7") (class "Default")
      (node (ref "LED20") (pin "A") (pinfunction "A_A") (pintype "passive"))
      (node (ref "MEGA2560PRO1") (pin "D44") (pinfunction "D44_D44") (pintype "bidirectional"))
      (node (ref "OK37") (pin "3") (pinfunction "EMIT_3") (pintype "passive"))
    )
    (net (code "27") (name "/IN8") (class "Default")
      (node (ref "LED19") (pin "A") (pinfunction "A_A") (pintype "passive"))
      (node (ref "MEGA2560PRO1") (pin "D46") (pinfunction "D46_D46") (pintype "bidirectional"))
      (node (ref "OK36") (pin "3") (pinfunction "EMIT_3") (pintype "passive"))
    )
    (net (code "28") (name "/IN9") (class "Default")
      (node (ref "LED18") (pin "A") (pinfunction "A_A") (pintype "passive"))
      (node (ref "MEGA2560PRO1") (pin "D47") (pinfunction "D47_D47") (pintype "bidirectional"))
      (node (ref "OK35") (pin "3") (pinfunction "EMIT_3") (pintype "passive"))
    )
    (net (code "29") (name "/IN10") (class "Default")
      (node (ref "LED17") (pin "A") (pinfunction "A_A") (pintype "passive"))
      (node (ref "MEGA2560PRO1") (pin "D48") (pinfunction "D48_D48") (pintype "bidirectional"))
      (node (ref "OK34") (pin "3") (pinfunction "EMIT_3") (pintype "passive"))
    )
    (net (code "30") (name "/IN11") (class "Default")
      (node (ref "LED16") (pin "A") (pinfunction "A_A") (pintype "passive"))
      (node (ref "MEGA2560PRO1") (pin "D50") (pinfunction "D50_D50") (pintype "bidirectional"))
      (node (ref "OK33") (pin "3") (pinfunction "EMIT_3") (pintype "passive"))
    )
    (net (code "31") (name "/IN12") (class "Default")
      (node (ref "LED15") (pin "A") (pinfunction "A_A") (pintype "passive"))
      (node (ref "MEGA2560PRO1") (pin "D52") (pinfunction "D52_D52") (pintype "bidirectional"))
      (node (ref "OK32") (pin "3") (pinfunction "EMIT_3") (pintype "passive"))
    )
    (net (code "32") (name "/IN13") (class "Default")
      (node (ref "LED14") (pin "A") (pinfunction "A_A") (pintype "passive"))
      (node (ref "MEGA2560PRO1") (pin "D53") (pinfunction "D53_D53") (pintype "bidirectional"))
      (node (ref "OK31") (pin "3") (pinfunction "EMIT_3") (pintype "passive"))
    )
    (net (code "33") (name "/IN14") (class "Default")
      (node (ref "LED13") (pin "A") (pinfunction "A_A") (pintype "passive"))
      (node (ref "MEGA2560PRO1") (pin "D51") (pinfunction "D51_D51") (pintype "bidirectional"))
      (node (ref "OK30") (pin "3") (pinfunction "EMIT_3") (pintype "passive"))
    )
    (net (code "34") (name "/MISO") (class "Default")
      (node (ref "JP8") (pin "4") (pinfunction "4_4") (pintype "passive"))
      (node (ref "MEGA2560PRO1") (pin "D33") (pinfunction "D33_D33") (pintype "bidirectional"))
      (node (ref "U$9") (pin "MISO") (pinfunction "MISO_MISO") (pintype "bidirectional"))
    )
    (net (code "35") (name "/MOSI") (class "Default")
      (node (ref "JP8") (pin "3") (pinfunction "3_3") (pintype "passive"))
      (node (ref "MEGA2560PRO1") (pin "D35") (pinfunction "D35_D35") (pintype "bidirectional"))
      (node (ref "U$9") (pin "MOSI") (pinfunction "MOSI_MOSI") (pintype "bidirectional"))
    )
    (net (code "36") (name "/OUT1") (class "Default")
      (node (ref "MEGA2560PRO1") (pin "D7") (pinfunction "D7_D7") (pintype "bidirectional"))
      (node (ref "OK29") (pin "2") (pinfunction "C_2") (pintype "passive"))
    )
    (net (code "37") (name "/OUT2") (class "Default")
      (node (ref "MEGA2560PRO1") (pin "D9") (pinfunction "D9_D9") (pintype "bidirectional"))
      (node (ref "OK24") (pin "2") (pinfunction "C_2") (pintype "passive"))
    )
    (net (code "38") (name "/OUT3") (class "Default")
      (node (ref "MEGA2560PRO1") (pin "D11") (pinfunction "D11_D11") (pintype "bidirectional"))
      (node (ref "OK25") (pin "2") (pinfunction "C_2") (pintype "passive"))
    )
    (net (code "39") (name "/OUT4") (class "Default")
      (node (ref "MEGA2560PRO1") (pin "D13") (pinfunction "D13_D13") (pintype "bidirectional"))
      (node (ref "OK26") (pin "2") (pinfunction "C_2") (pintype "passive"))
    )
    (net (code "40") (name "/OUT5") (class "Default")
      (node (ref "MEGA2560PRO1") (pin "D15") (pinfunction "D15_D15") (pintype "bidirectional"))
      (node (ref "OK27") (pin "2") (pinfunction "C_2") (pintype "passive"))
    )
    (net (code "41") (name "/OUT6") (class "Default")
      (node (ref "MEGA2560PRO1") (pin "D17") (pinfunction "D17_D17") (pintype "bidirectional"))
      (node (ref "OK28") (pin "2") (pinfunction "C_2") (pintype "passive"))
    )
    (net (code "42") (name "/R1") (class "Default")
      (node (ref "MEGA2560PRO1") (pin "D3") (pinfunction "D3_D3") (pintype "bidirectional"))
      (node (ref "R18") (pin "2") (pinfunction "2_2") (pintype "passive"))
    )
    (net (code "43") (name "/R2") (class "Default")
      (node (ref "MEGA2560PRO1") (pin "D5") (pinfunction "D5_D5") (pintype "bidirectional"))
      (node (ref "R21") (pin "2") (pinfunction "2_2") (pintype "passive"))
    )
    (net (code "44") (name "/RESETESP") (class "Default")
      (node (ref "MEGA2560PRO1") (pin "D49") (pinfunction "D49_D49") (pintype "bidirectional"))
      (node (ref "R5") (pin "2") (pinfunction "2_2") (pintype "passive"))
    )
    (net (code "45") (name "/RX1") (class "Default")
      (node (ref "JP29") (pin "4") (pinfunction "4_4") (pintype "passive"))
      (node (ref "MEGA2560PRO1") (pin "D12") (pinfunction "D12_D12") (pintype "bidirectional"))
    )
    (net (code "46") (name "/RX2") (class "Default")
      (node (ref "MEGA2560PRO1") (pin "D43") (pinfunction "D43_D43") (pintype "bidirectional"))
      (node (ref "R8") (pin "1") (pinfunction "1_1") (pintype "passive"))
      (node (ref "T1") (pin "C") (pinfunction "C_C") (pintype "passive"))
    )
    (net (code "47") (name "/RX3") (class "Default")
      (node (ref "MEGA2560PRO1") (pin "D4") (pinfunction "D4_D4") (pintype "bidirectional"))
      (node (ref "U$4") (pin "5") (pinfunction "RXD_5") (pintype "bidirectional"))
    )
    (net (code "48") (name "/SCK") (class "Default")
      (node (ref "JP8") (pin "2") (pinfunction "2_2") (pintype "passive"))
      (node (ref "MEGA2560PRO1") (pin "D37") (pinfunction "D37_D37") (pintype "bidirectional"))
      (node (ref "U$9") (pin "SCK") (pinfunction "SCK_SCK") (pintype "bidirectional"))
    )
    (net (code "49") (name "/SCL") (class "Default")
      (node (ref "JP10") (pin "3") (pinfunction "3_3") (pintype "passive"))
      (node (ref "JP32") (pin "3") (pinfunction "3_3") (pintype "passive"))
      (node (ref "MEGA2560PRO1") (pin "D16") (pinfunction "D16_D16") (pintype "bidirectional"))
    )
    (net (code "50") (name "/SDA") (class "Default")
      (node (ref "JP10") (pin "2") (pinfunction "2_2") (pintype "passive"))
      (node (ref "JP32") (pin "2") (pinfunction "2_2") (pintype "passive"))
      (node (ref "MEGA2560PRO1") (pin "D18") (pinfunction "D18_D18") (pintype "bidirectional"))
    )
    (net (code "51") (name "/SDCS") (class "Default")
      (node (ref "MEGA2560PRO1") (pin "D41") (pinfunction "D41_D41") (pintype "bidirectional"))
      (node (ref "U$9") (pin "CS") (pinfunction "CS_CS") (pintype "bidirectional"))
    )
    (net (code "52") (name "/STEP_A") (class "Default")
      (node (ref "MEGA2560PRO1") (pin "D30") (pinfunction "D30_D30") (pintype "bidirectional"))
      (node (ref "OK16") (pin "2") (pinfunction "C_2") (pintype "passive"))
    )
    (net (code "53") (name "/STEP_B") (class "Default")
      (node (ref "MEGA2560PRO1") (pin "D26") (pinfunction "D26_D26") (pintype "bidirectional"))
      (node (ref "OK18") (pin "2") (pinfunction "C_2") (pintype "passive"))
    )
    (net (code "54") (name "/STEP_C") (class "Default")
      (node (ref "MEGA2560PRO1") (pin "D22") (pinfunction "D22_D22") (pintype "bidirectional"))
      (node (ref "OK20") (pin "2") (pinfunction "C_2") (pintype "passive"))
    )
    (net (code "55") (name "/STEP_X") (class "Default")
      (node (ref "MEGA2560PRO1") (pin "D21") (pinfunction "D21_D21") (pintype "bidirectional"))
      (node (ref "OK23") (pin "2") (pinfunction "C_2") (pintype "passive"))
    )
    (net (code "56") (name "/STEP_Y") (class "Default")
      (node (ref "MEGA2560PRO1") (pin "D25") (pinfunction "D25_D25") (pintype "bidirectional"))
      (node (ref "OK12") (pin "2") (pinfunction "C_2") (pintype "passive"))
    )
    (net (code "57") (name "/STEP_Z") (class "Default")
      (node (ref "MEGA2560PRO1") (pin "D29") (pinfunction "D29_D29") (pintype "bidirectional"))
      (node (ref "OK14") (pin "2") (pinfunction "C_2") (pintype "passive"))
    )
    (net (code "58") (name "/TX1") (class "Default")
      (node (ref "JP29") (pin "3") (pinfunction "3_3") (pintype "passive"))
      (node (ref "MEGA2560PRO1") (pin "D14") (pinfunction "D14_D14") (pintype "bidirectional"))
    )
    (net (code "59") (name "/TX2") (class "Default")
      (node (ref "MEGA2560PRO1") (pin "D45") (pinfunction "D45_D45") (pintype "bidirectional"))
      (node (ref "R3") (pin "2") (pinfunction "2_2") (pintype "passive"))
    )
    (net (code "60") (name "/TX3") (class "Default")
      (node (ref "MEGA2560PRO1") (pin "D2") (pinfunction "D2_D2") (pintype "bidirectional"))
      (node (ref "U$4") (pin "4") (pinfunction "TXD_4") (pintype "bidirectional"))
    )
    (net (code "61") (name "GND") (class "Default")
      (node (ref "C1") (pin "-") (pinfunction "-_-") (pintype "passive"))
      (node (ref "C2") (pin "-") (pinfunction "-_-") (pintype "passive"))
      (node (ref "JP10") (pin "5") (pinfunction "5_5") (pintype "passive"))
      (node (ref "JP29") (pin "2") (pinfunction "2_2") (pintype "passive"))
      (node (ref "JP32") (pin "4") (pinfunction "4_4") (pintype "passive"))
      (node (ref "JP8") (pin "6") (pinfunction "6_6") (pintype "passive"))
      (node (ref "K1") (pin "4") (pinfunction "-_4") (pintype "power_in"))
      (node (ref "K2") (pin "4") (pinfunction "-_4") (pintype "power_in"))
      (node (ref "MEGA2560PRO1") (pin "GND@1") (pinfunction "GND_GND@1") (pintype "bidirectional"))
      (node (ref "MEGA2560PRO1") (pin "GND@2") (pinfunction "GND_GND@2") (pintype "bidirectional"))
      (node (ref "OK30") (pin "2") (pinfunction "C_2") (pintype "passive"))
      (node (ref "OK31") (pin "2") (pinfunction "C_2") (pintype "passive"))
      (node (ref "OK32") (pin "2") (pinfunction "C_2") (pintype "passive"))
      (node (ref "OK33") (pin "2") (pinfunction "C_2") (pintype "passive"))
      (node (ref "OK34") (pin "2") (pinfunction "C_2") (pintype "passive"))
      (node (ref "OK35") (pin "2") (pinfunction "C_2") (pintype "passive"))
      (node (ref "OK36") (pin "2") (pinfunction "C_2") (pintype "passive"))
      (node (ref "OK37") (pin "2") (pinfunction "C_2") (pintype "passive"))
      (node (ref "OK38") (pin "2") (pinfunction "C_2") (pintype "passive"))
      (node (ref "OK39") (pin "2") (pinfunction "C_2") (pintype "passive"))
      (node (ref "OK40") (pin "2") (pinfunction "C_2") (pintype "passive"))
      (node (ref "OK41") (pin "2") (pinfunction "C_2") (pintype "passive"))
      (node (ref "OK42") (pin "2") (pinfunction "C_2") (pintype "passive"))
      (node (ref "OK43") (pin "2") (pinfunction "C_2") (pintype "passive"))
      (node (ref "R1") (pin "1") (pinfunction "1_1") (pintype "passive"))
      (node (ref "R10") (pin "1") (pinfunction "1_1") (pintype "passive"))
      (node (ref "R12") (pin "1") (pinfunction "1_1") (pintype "passive"))
      (node (ref "R14") (pin "1") (pinfunction "1_1") (pintype "passive"))
      (node (ref "R16") (pin "1") (pinfunction "1_1") (pintype "passive"))
      (node (ref "R17") (pin "1") (pinfunction "1_1") (pintype "passive"))
      (node (ref "R20") (pin "1") (pinfunction "1_1") (pintype "passive"))
      (node (ref "R4") (pin "1") (pinfunction "1_1") (pintype "passive"))
      (node (ref "R6") (pin "1") (pinfunction "1_1") (pintype "passive"))
      (node (ref "R72") (pin "1") (pinfunction "1_1") (pintype "passive"))
      (node (ref "R74") (pin "1") (pinfunction "1_1") (pintype "passive"))
      (node (ref "R76") (pin "1") (pinfunction "1_1") (pintype "passive"))
      (node (ref "R78") (pin "1") (pinfunction "1_1") (pintype "passive"))
      (node (ref "R80") (pin "1") (pinfunction "1_1") (pintype "passive"))
      (node (ref "R82") (pin "1") (pinfunction "1_1") (pintype "passive"))
      (node (ref "R84") (pin "1") (pinfunction "1_1") (pintype "passive"))
      (node (ref "R86") (pin "1") (pinfunction "1_1") (pintype "passive"))
      (node (ref "R88") (pin "1") (pinfunction "1_1") (pintype "passive"))
      (node (ref "R90") (pin "1") (pinfunction "1_1") (pintype "passive"))
      (node (ref "R92") (pin "1") (pinfunction "1_1") (pintype "passive"))
      (node (ref "R94") (pin "1") (pinfunction "1_1") (pintype "passive"))
      (node (ref "R96") (pin "1") (pinfunction "1_1") (pintype "passive"))
      (node (ref "R98") (pin "1") (pinfunction "1_1") (pintype "passive"))
      (node (ref "T2") (pin "E") (pinfunction "E_E") (pintype "passive"))
      (node (ref "T3") (pin "E") (pinfunction "E_E") (pintype "passive"))
      (node (ref "U$1") (pin "OUT-") (pinfunction "OUT-_OUT-") (pintype "bidirectional"))
      (node (ref "U$2") (pin "A1") (pinfunction "GND_A1") (pintype "power_in"))
      (node (ref "U$3") (pin "OUT-") (pinfunction "OUT-_OUT-") (pintype "bidirectional"))
      (node (ref "U$4") (pin "2") (pinfunction "GND_2") (pintype "bidirectional"))
      (node (ref "U$4") (pin "6") (pinfunction "GND_6") (pintype "bidirectional"))
      (node (ref "U$9") (pin "GND") (pinfunction "GND_GND") (pintype "bidirectional"))
      (node (ref "X4") (pin "20") (pinfunction "S_20") (pintype "passive"))
      (node (ref "X5") (pin "2") (pinfunction "S_2") (pintype "passive"))
      (node (ref "X6") (pin "2") (pinfunction "S_2") (pintype "passive"))
      (node (ref "X7") (pin "7") (pinfunction "S_7") (pintype "passive"))
      (node (ref "X8") (pin "1") (pinfunction "S_1") (pintype "passive"))
    )
    (net (code "62") (name "Net-(IC1-ADJ)") (class "Default")
      (node (ref "IC1") (pin "1") (pinfunction "ADJ_1") (pintype "input"))
      (node (ref "R1") (pin "2") (pinfunction "2_2") (pintype "passive"))
      (node (ref "R2") (pin "1") (pinfunction "1_1") (pintype "passive"))
    )
    (net (code "63") (name "Net-(INA-S)") (class "Default")
      (node (ref "IN") (pin "1") (pinfunction "S_1") (pintype "passive"))
      (node (ref "R97") (pin "2") (pinfunction "2_2") (pintype "passive"))
    )
    (net (code "64") (name "Net-(INB-S)") (class "Default")
      (node (ref "IN") (pin "10") (pinfunction "S_10") (pintype "passive"))
      (node (ref "R79") (pin "2") (pinfunction "2_2") (pintype "passive"))
    )
    (net (code "65") (name "Net-(INC-S)") (class "Default")
      (node (ref "IN") (pin "11") (pinfunction "S_11") (pintype "passive"))
      (node (ref "R77") (pin "2") (pinfunction "2_2") (pintype "passive"))
    )
    (net (code "66") (name "Net-(IND-S)") (class "Default")
      (node (ref "IN") (pin "12") (pinfunction "S_12") (pintype "passive"))
      (node (ref "R75") (pin "2") (pinfunction "2_2") (pintype "passive"))
    )
    (net (code "67") (name "Net-(INE-S)") (class "Default")
      (node (ref "IN") (pin "13") (pinfunction "S_13") (pintype "passive"))
      (node (ref "R73") (pin "2") (pinfunction "2_2") (pintype "passive"))
    )
    (net (code "68") (name "Net-(INF-S)") (class "Default")
      (node (ref "IN") (pin "14") (pinfunction "S_14") (pintype "passive"))
      (node (ref "R24") (pin "2") (pinfunction "2_2") (pintype "passive"))
    )
    (net (code "69") (name "Net-(ING-S)") (class "Default")
      (node (ref "IN") (pin "2") (pinfunction "S_2") (pintype "passive"))
      (node (ref "R95") (pin "2") (pinfunction "2_2") (pintype "passive"))
    )
    (net (code "70") (name "Net-(INH-S)") (class "Default")
      (node (ref "IN") (pin "3") (pinfunction "S_3") (pintype "passive"))
      (node (ref "R93") (pin "2") (pinfunction "2_2") (pintype "passive"))
    )
    (net (code "71") (name "Net-(INI-S)") (class "Default")
      (node (ref "IN") (pin "4") (pinfunction "S_4") (pintype "passive"))
      (node (ref "R91") (pin "2") (pinfunction "2_2") (pintype "passive"))
    )
    (net (code "72") (name "Net-(INJ-S)") (class "Default")
      (node (ref "IN") (pin "5") (pinfunction "S_5") (pintype "passive"))
      (node (ref "R89") (pin "2") (pinfunction "2_2") (pintype "passive"))
    )
    (net (code "73") (name "Net-(INK-S)") (class "Default")
      (node (ref "IN") (pin "6") (pinfunction "S_6") (pintype "passive"))
      (node (ref "R87") (pin "2") (pinfunction "2_2") (pintype "passive"))
    )
    (net (code "74") (name "Net-(INL-S)") (class "Default")
      (node (ref "IN") (pin "7") (pinfunction "S_7") (pintype "passive"))
      (node (ref "R85") (pin "2") (pinfunction "2_2") (pintype "passive"))
    )
    (net (code "75") (name "Net-(INM-S)") (class "Default")
      (node (ref "IN") (pin "8") (pinfunction "S_8") (pintype "passive"))
      (node (ref "R83") (pin "2") (pinfunction "2_2") (pintype "passive"))
    )
    (net (code "76") (name "Net-(INN-S)") (class "Default")
      (node (ref "IN") (pin "9") (pinfunction "S_9") (pintype "passive"))
      (node (ref "R81") (pin "2") (pinfunction "2_2") (pintype "passive"))
    )
    (net (code "77") (name "Net-(K1-L1)") (class "Default")
      (node (ref "K1") (pin "1") (pinfunction "L1_1") (pintype "power_in"))
      (node (ref "X2") (pin "1") (pinfunction "KL_1") (pintype "passive"))
    )
    (net (code "78") (name "Net-(K1-L2)") (class "Default")
      (node (ref "K1") (pin "2") (pinfunction "L2_2") (pintype "power_in"))
      (node (ref "X2") (pin "2") (pinfunction "KL_2") (pintype "passive"))
    )
    (net (code "79") (name "Net-(K2-L1)") (class "Default")
      (node (ref "K2") (pin "1") (pinfunction "L1_1") (pintype "power_in"))
      (node (ref "X3") (pin "1") (pinfunction "KL_1") (pintype "passive"))
    )
    (net (code "80") (name "Net-(K2-L2)") (class "Default")
      (node (ref "K2") (pin "2") (pinfunction "L2_2") (pintype "power_in"))
      (node (ref "X3") (pin "2") (pinfunction "KL_2") (pintype "passive"))
    )
    (net (code "81") (name "Net-(LED1-C)") (class "Default")
      (node (ref "LED1") (pin "K") (pinfunction "C_K") (pintype "passive"))
      (node (ref "T2") (pin "C") (pinfunction "C_C") (pintype "passive"))
    )
    (net (code "82") (name "Net-(LED1-PadA)") (class "Default")
      (node (ref "LED1") (pin "A") (pinfunction "A_A") (pintype "passive"))
      (node (ref "R19") (pin "1") (pinfunction "1_1") (pintype "passive"))
    )
    (net (code "83") (name "Net-(LED2-C)") (class "Default")
      (node (ref "LED2") (pin "K") (pinfunction "C_K") (pintype "passive"))
      (node (ref "T3") (pin "C") (pinfunction "C_C") (pintype "passive"))
    )
    (net (code "84") (name "Net-(LED2-PadA)") (class "Default")
      (node (ref "LED2") (pin "A") (pinfunction "A_A") (pintype "passive"))
      (node (ref "R22") (pin "1") (pinfunction "1_1") (pintype "passive"))
    )
    (net (code "85") (name "Net-(LED13-C)") (class "Default")
      (node (ref "LED13") (pin "K") (pinfunction "C_K") (pintype "passive"))
      (node (ref "R72") (pin "2") (pinfunction "2_2") (pintype "passive"))
    )
    (net (code "86") (name "Net-(LED14-C)") (class "Default")
      (node (ref "LED14") (pin "K") (pinfunction "C_K") (pintype "passive"))
      (node (ref "R74") (pin "2") (pinfunction "2_2") (pintype "passive"))
    )
    (net (code "87") (name "Net-(LED15-C)") (class "Default")
      (node (ref "LED15") (pin "K") (pinfunction "C_K") (pintype "passive"))
      (node (ref "R76") (pin "2") (pinfunction "2_2") (pintype "passive"))
    )
    (net (code "88") (name "Net-(LED16-C)") (class "Default")
      (node (ref "LED16") (pin "K") (pinfunction "C_K") (pintype "passive"))
      (node (ref "R78") (pin "2") (pinfunction "2_2") (pintype "passive"))
    )
    (net (code "89") (name "Net-(LED17-C)") (class "Default")
      (node (ref "LED17") (pin "K") (pinfunction "C_K") (pintype "passive"))
      (node (ref "R80") (pin "2") (pinfunction "2_2") (pintype "passive"))
    )
    (net (code "90") (name "Net-(LED18-C)") (class "Default")
      (node (ref "LED18") (pin "K") (pinfunction "C_K") (pintype "passive"))
      (node (ref "R82") (pin "2") (pinfunction "2_2") (pintype "passive"))
    )
    (net (code "91") (name "Net-(LED19-C)") (class "Default")
      (node (ref "LED19") (pin "K") (pinfunction "C_K") (pintype "passive"))
      (node (ref "R84") (pin "2") (pinfunction "2_2") (pintype "passive"))
    )
    (net (code "92") (name "Net-(LED20-C)") (class "Default")
      (node (ref "LED20") (pin "K") (pinfunction "C_K") (pintype "passive"))
      (node (ref "R86") (pin "2") (pinfunction "2_2") (pintype "passive"))
    )
    (net (code "93") (name "Net-(LED21-C)") (class "Default")
      (node (ref "LED21") (pin "K") (pinfunction "C_K") (pintype "passive"))
      (node (ref "R88") (pin "2") (pinfunction "2_2") (pintype "passive"))
    )
    (net (code "94") (name "Net-(LED22-C)") (class "Default")
      (node (ref "LED22") (pin "K") (pinfunction "C_K") (pintype "passive"))
      (node (ref "R90") (pin "2") (pinfunction "2_2") (pintype "passive"))
    )
    (net (code "95") (name "Net-(LED23-C)") (class "Default")
      (node (ref "LED23") (pin "K") (pinfunction "C_K") (pintype "passive"))
      (node (ref "R92") (pin "2") (pinfunction "2_2") (pintype "passive"))
    )
    (net (code "96") (name "Net-(LED24-C)") (class "Default")
      (node (ref "LED24") (pin "K") (pinfunction "C_K") (pintype "passive"))
      (node (ref "R94") (pin "2") (pinfunction "2_2") (pintype "passive"))
    )
    (net (code "97") (name "Net-(LED25-C)") (class "Default")
      (node (ref "LED25") (pin "K") (pinfunction "C_K") (pintype "passive"))
      (node (ref "R96") (pin "2") (pinfunction "2_2") (pintype "passive"))
    )
    (net (code "98") (name "Net-(LED26-C)") (class "Default")
      (node (ref "LED26") (pin "K") (pinfunction "C_K") (pintype "passive"))
      (node (ref "R98") (pin "2") (pinfunction "2_2") (pintype "passive"))
    )
    (net (code "99") (name "Net-(OK11-A)") (class "Default")
      (node (ref "OK11") (pin "1") (pinfunction "A_1") (pintype "passive"))
      (node (ref "R53") (pin "2") (pinfunction "2_2") (pintype "passive"))
    )
    (net (code "100") (name "Net-(OK11-EMIT)") (class "Default")
      (node (ref "OK11") (pin "3") (pinfunction "EMIT_3") (pintype "passive"))
      (node (ref "X4") (pin "3") (pinfunction "S_3") (pintype "passive"))
    )
    (net (code "101") (name "Net-(OK12-A)") (class "Default")
      (node (ref "OK12") (pin "1") (pinfunction "A_1") (pintype "passive"))
      (node (ref "R55") (pin "2") (pinfunction "2_2") (pintype "passive"))
    )
    (net (code "102") (name "Net-(OK12-EMIT)") (class "Default")
      (node (ref "OK12") (pin "3") (pinfunction "EMIT_3") (pintype "passive"))
      (node (ref "X4") (pin "5") (pinfunction "S_5") (pintype "passive"))
    )
    (net (code "103") (name "Net-(OK13-A)") (class "Default")
      (node (ref "OK13") (pin "1") (pinfunction "A_1") (pintype "passive"))
      (node (ref "R56") (pin "2") (pinfunction "2_2") (pintype "passive"))
    )
    (net (code "104") (name "Net-(OK13-EMIT)") (class "Default")
      (node (ref "OK13") (pin "3") (pinfunction "EMIT_3") (pintype "passive"))
      (node (ref "X4") (pin "6") (pinfunction "S_6") (pintype "passive"))
    )
    (net (code "105") (name "Net-(OK14-A)") (class "Default")
      (node (ref "OK14") (pin "1") (pinfunction "A_1") (pintype "passive"))
      (node (ref "R57") (pin "2") (pinfunction "2_2") (pintype "passive"))
    )
    (net (code "106") (name "Net-(OK14-EMIT)") (class "Default")
      (node (ref "OK14") (pin "3") (pinfunction "EMIT_3") (pintype "passive"))
      (node (ref "X4") (pin "8") (pinfunction "S_8") (pintype "passive"))
    )
    (net (code "107") (name "Net-(OK15-A)") (class "Default")
      (node (ref "OK15") (pin "1") (pinfunction "A_1") (pintype "passive"))
      (node (ref "R58") (pin "2") (pinfunction "2_2") (pintype "passive"))
    )
    (net (code "108") (name "Net-(OK15-EMIT)") (class "Default")
      (node (ref "OK15") (pin "3") (pinfunction "EMIT_3") (pintype "passive"))
      (node (ref "X4") (pin "9") (pinfunction "S_9") (pintype "passive"))
    )
    (net (code "109") (name "Net-(OK16-A)") (class "Default")
      (node (ref "OK16") (pin "1") (pinfunction "A_1") (pintype "passive"))
      (node (ref "R59") (pin "2") (pinfunction "2_2") (pintype "passive"))
    )
    (net (code "110") (name "Net-(OK16-EMIT)") (class "Default")
      (node (ref "OK16") (pin "3") (pinfunction "EMIT_3") (pintype "passive"))
      (node (ref "X4") (pin "11") (pinfunction "S_11") (pintype "passive"))
    )
    (net (code "111") (name "Net-(OK17-A)") (class "Default")
      (node (ref "OK17") (pin "1") (pinfunction "A_1") (pintype "passive"))
      (node (ref "R60") (pin "2") (pinfunction "2_2") (pintype "passive"))
    )
    (net (code "112") (name "Net-(OK17-EMIT)") (class "Default")
      (node (ref "OK17") (pin "3") (pinfunction "EMIT_3") (pintype "passive"))
      (node (ref "X4") (pin "12") (pinfunction "S_12") (pintype "passive"))
    )
    (net (code "113") (name "Net-(OK18-A)") (class "Default")
      (node (ref "OK18") (pin "1") (pinfunction "A_1") (pintype "passive"))
      (node (ref "R61") (pin "2") (pinfunction "2_2") (pintype "passive"))
    )
    (net (code "114") (name "Net-(OK18-EMIT)") (class "Default")
      (node (ref "OK18") (pin "3") (pinfunction "EMIT_3") (pintype "passive"))
      (node (ref "X4") (pin "14") (pinfunction "S_14") (pintype "passive"))
    )
    (net (code "115") (name "Net-(OK19-A)") (class "Default")
      (node (ref "OK19") (pin "1") (pinfunction "A_1") (pintype "passive"))
      (node (ref "R62") (pin "2") (pinfunction "2_2") (pintype "passive"))
    )
    (net (code "116") (name "Net-(OK19-EMIT)") (class "Default")
      (node (ref "OK19") (pin "3") (pinfunction "EMIT_3") (pintype "passive"))
      (node (ref "X4") (pin "15") (pinfunction "S_15") (pintype "passive"))
    )
    (net (code "117") (name "Net-(OK20-A)") (class "Default")
      (node (ref "OK20") (pin "1") (pinfunction "A_1") (pintype "passive"))
      (node (ref "R63") (pin "2") (pinfunction "2_2") (pintype "passive"))
    )
    (net (code "118") (name "Net-(OK20-EMIT)") (class "Default")
      (node (ref "OK20") (pin "3") (pinfunction "EMIT_3") (pintype "passive"))
      (node (ref "X4") (pin "17") (pinfunction "S_17") (pintype "passive"))
    )
    (net (code "119") (name "Net-(OK21-A)") (class "Default")
      (node (ref "OK21") (pin "1") (pinfunction "A_1") (pintype "passive"))
      (node (ref "R64") (pin "2") (pinfunction "2_2") (pintype "passive"))
    )
    (net (code "120") (name "Net-(OK21-EMIT)") (class "Default")
      (node (ref "OK21") (pin "3") (pinfunction "EMIT_3") (pintype "passive"))
      (node (ref "X4") (pin "18") (pinfunction "S_18") (pintype "passive"))
    )
    (net (code "121") (name "Net-(OK22-A)") (class "Default")
      (node (ref "OK22") (pin "1") (pinfunction "A_1") (pintype "passive"))
      (node (ref "R65") (pin "2") (pinfunction "2_2") (pintype "passive"))
    )
    (net (code "122") (name "Net-(OK23-A)") (class "Default")
      (node (ref "OK23") (pin "1") (pinfunction "A_1") (pintype "passive"))
      (node (ref "R54") (pin "2") (pinfunction "2_2") (pintype "passive"))
    )
    (net (code "123") (name "Net-(OK23-EMIT)") (class "Default")
      (node (ref "OK23") (pin "3") (pinfunction "EMIT_3") (pintype "passive"))
      (node (ref "X4") (pin "2") (pinfunction "S_2") (pintype "passive"))
    )
    (net (code "124") (name "Net-(OK24-A)") (class "Default")
      (node (ref "OK24") (pin "1") (pinfunction "A_1") (pintype "passive"))
      (node (ref "R66") (pin "2") (pinfunction "2_2") (pintype "passive"))
    )
    (net (code "125") (name "Net-(OK24-EMIT)") (class "Default")
      (node (ref "OK24") (pin "3") (pinfunction "EMIT_3") (pintype "passive"))
      (node (ref "X7") (pin "2") (pinfunction "S_2") (pintype "passive"))
    )
    (net (code "126") (name "Net-(OK25-A)") (class "Default")
      (node (ref "OK25") (pin "1") (pinfunction "A_1") (pintype "passive"))
      (node (ref "R68") (pin "2") (pinfunction "2_2") (pintype "passive"))
    )
    (net (code "127") (name "Net-(OK25-EMIT)") (class "Default")
      (node (ref "OK25") (pin "3") (pinfunction "EMIT_3") (pintype "passive"))
      (node (ref "X7") (pin "3") (pinfunction "S_3") (pintype "passive"))
    )
    (net (code "128") (name "Net-(OK26-A)") (class "Default")
      (node (ref "OK26") (pin "1") (pinfunction "A_1") (pintype "passive"))
      (node (ref "R69") (pin "2") (pinfunction "2_2") (pintype "passive"))
    )
    (net (code "129") (name "Net-(OK26-EMIT)") (class "Default")
      (node (ref "OK26") (pin "3") (pinfunction "EMIT_3") (pintype "passive"))
      (node (ref "X7") (pin "4") (pinfunction "S_4") (pintype "passive"))
    )
    (net (code "130") (name "Net-(OK27-A)") (class "Default")
      (node (ref "OK27") (pin "1") (pinfunction "A_1") (pintype "passive"))
      (node (ref "R70") (pin "2") (pinfunction "2_2") (pintype "passive"))
    )
    (net (code "131") (name "Net-(OK27-EMIT)") (class "Default")
      (node (ref "OK27") (pin "3") (pinfunction "EMIT_3") (pintype "passive"))
      (node (ref "X7") (pin "5") (pinfunction "S_5") (pintype "passive"))
    )
    (net (code "132") (name "Net-(OK28-A)") (class "Default")
      (node (ref "OK28") (pin "1") (pinfunction "A_1") (pintype "passive"))
      (node (ref "R71") (pin "2") (pinfunction "2_2") (pintype "passive"))
    )
    (net (code "133") (name "Net-(OK28-EMIT)") (class "Default")
      (node (ref "OK28") (pin "3") (pinfunction "EMIT_3") (pintype "passive"))
      (node (ref "X7") (pin "6") (pinfunction "S_6") (pintype "passive"))
    )
    (net (code "134") (name "Net-(OK29-A)") (class "Default")
      (node (ref "OK29") (pin "1") (pinfunction "A_1") (pintype "passive"))
      (node (ref "R67") (pin "2") (pinfunction "2_2") (pintype "passive"))
    )
    (net (code "135") (name "Net-(OK29-EMIT)") (class "Default")
      (node (ref "OK29") (pin "3") (pinfunction "EMIT_3") (pintype "passive"))
      (node (ref "X7") (pin "1") (pinfunction "S_1") (pintype "passive"))
    )
    (net (code "136") (name "Net-(OK30-A)") (class "Default")
      (node (ref "OK30") (pin "1") (pinfunction "A_1") (pintype "passive"))
      (node (ref "R24") (pin "1") (pinfunction "1_1") (pintype "passive"))
    )
    (net (code "137") (name "Net-(OK31-A)") (class "Default")
      (node (ref "OK31") (pin "1") (pinfunction "A_1") (pintype "passive"))
      (node (ref "R73") (pin "1") (pinfunction "1_1") (pintype "passive"))
    )
    (net (code "138") (name "Net-(OK32-A)") (class "Default")
      (node (ref "OK32") (pin "1") (pinfunction "A_1") (pintype "passive"))
      (node (ref "R75") (pin "1") (pinfunction "1_1") (pintype "passive"))
    )
    (net (code "139") (name "Net-(OK33-A)") (class "Default")
      (node (ref "OK33") (pin "1") (pinfunction "A_1") (pintype "passive"))
      (node (ref "R77") (pin "1") (pinfunction "1_1") (pintype "passive"))
    )
    (net (code "140") (name "Net-(OK34-A)") (class "Default")
      (node (ref "OK34") (pin "1") (pinfunction "A_1") (pintype "passive"))
      (node (ref "R79") (pin "1") (pinfunction "1_1") (pintype "passive"))
    )
    (net (code "141") (name "Net-(OK35-A)") (class "Default")
      (node (ref "OK35") (pin "1") (pinfunction "A_1") (pintype "passive"))
      (node (ref "R81") (pin "1") (pinfunction "1_1") (pintype "passive"))
    )
    (net (code "142") (name "Net-(OK36-A)") (class "Default")
      (node (ref "OK36") (pin "1") (pinfunction "A_1") (pintype "passive"))
      (node (ref "R83") (pin "1") (pinfunction "1_1") (pintype "passive"))
    )
    (net (code "143") (name "Net-(OK37-A)") (class "Default")
      (node (ref "OK37") (pin "1") (pinfunction "A_1") (pintype "passive"))
      (node (ref "R85") (pin "1") (pinfunction "1_1") (pintype "passive"))
    )
    (net (code "144") (name "Net-(OK38-A)") (class "Default")
      (node (ref "OK38") (pin "1") (pinfunction "A_1") (pintype "passive"))
      (node (ref "R87") (pin "1") (pinfunction "1_1") (pintype "passive"))
    )
    (net (code "145") (name "Net-(OK39-A)") (class "Default")
      (node (ref "OK39") (pin "1") (pinfunction "A_1") (pintype "passive"))
      (node (ref "R89") (pin "1") (pinfunction "1_1") (pintype "passive"))
    )
    (net (code "146") (name "Net-(OK40-A)") (class "Default")
      (node (ref "OK40") (pin "1") (pinfunction "A_1") (pintype "passive"))
      (node (ref "R91") (pin "1") (pinfunction "1_1") (pintype "passive"))
    )
    (net (code "147") (name "Net-(OK41-A)") (class "Default")
      (node (ref "OK41") (pin "1") (pinfunction "A_1") (pintype "passive"))
      (node (ref "R93") (pin "1") (pinfunction "1_1") (pintype "passive"))
    )
    (net (code "148") (name "Net-(OK42-A)") (class "Default")
      (node (ref "OK42") (pin "1") (pinfunction "A_1") (pintype "passive"))
      (node (ref "R95") (pin "1") (pinfunction "1_1") (pintype "passive"))
    )
    (net (code "149") (name "Net-(OK43-A)") (class "Default")
      (node (ref "OK43") (pin "1") (pinfunction "A_1") (pintype "passive"))
      (node (ref "R97") (pin "1") (pinfunction "1_1") (pintype "passive"))
    )
    (net (code "150") (name "Net-(R7-Pad1)") (class "Default")
      (node (ref "R7") (pin "1") (pinfunction "1_1") (pintype "passive"))
      (node (ref "T1") (pin "B") (pinfunction "B_B") (pintype "passive"))
    )
    (net (code "151") (name "Net-(R17-Pad2)") (class "Default")
      (node (ref "R17") (pin "2") (pinfunction "2_2") (pintype "passive"))
      (node (ref "R18") (pin "1") (pinfunction "1_1") (pintype "passive"))
      (node (ref "T2") (pin "B") (pinfunction "B_B") (pintype "passive"))
    )
    (net (code "152") (name "Net-(R20-Pad2)") (class "Default")
      (node (ref "R20") (pin "2") (pinfunction "2_2") (pintype "passive"))
      (node (ref "R21") (pin "1") (pinfunction "1_1") (pintype "passive"))
      (node (ref "T3") (pin "B") (pinfunction "B_B") (pintype "passive"))
    )
    (net (code "153") (name "Net-(X1A-KL)") (class "Default")
      (node (ref "U$1") (pin "IN+") (pinfunction "IN+_IN+") (pintype "bidirectional"))
      (node (ref "U$3") (pin "IN+") (pinfunction "IN+_IN+") (pintype "bidirectional"))
      (node (ref "X1") (pin "1") (pinfunction "KL_1") (pintype "passive"))
    )
    (net (code "154") (name "Net-(X1B-KL)") (class "Default")
      (node (ref "U$1") (pin "IN-") (pinfunction "IN-_IN-") (pintype "bidirectional"))
      (node (ref "U$3") (pin "IN-") (pinfunction "IN-_IN-") (pintype "bidirectional"))
      (node (ref "X1") (pin "2") (pinfunction "KL_2") (pintype "passive"))
    )
    (net (code "155") (name "Net-(X8C-S)") (class "Default")
      (node (ref "R15") (pin "2") (pinfunction "2_2") (pintype "passive"))
      (node (ref "X8") (pin "3") (pinfunction "S_3") (pintype "passive"))
    )
    (net (code "156") (name "Net-(X8D-S)") (class "Default")
      (node (ref "R13") (pin "2") (pinfunction "2_2") (pintype "passive"))
      (node (ref "X8") (pin "4") (pinfunction "S_4") (pintype "passive"))
    )
    (net (code "157") (name "Net-(X8E-S)") (class "Default")
      (node (ref "R11") (pin "2") (pinfunction "2_2") (pintype "passive"))
      (node (ref "X8") (pin "5") (pinfunction "S_5") (pintype "passive"))
    )
    (net (code "158") (name "Net-(X8F-S)") (class "Default")
      (node (ref "R9") (pin "2") (pinfunction "2_2") (pintype "passive"))
      (node (ref "X8") (pin "6") (pinfunction "S_6") (pintype "passive"))
    )
    (net (code "159") (name "unconnected-(JP10-Pad4)") (class "Default")
      (node (ref "JP10") (pin "4") (pinfunction "4_4") (pintype "passive"))
    )
    (net (code "160") (name "unconnected-(MEGA2560PRO1-5V-Pad5V@3)") (class "Default")
      (node (ref "MEGA2560PRO1") (pin "5V@3") (pinfunction "5V_5V@3") (pintype "bidirectional"))
    )
    (net (code "161") (name "unconnected-(MEGA2560PRO1-GND-PadGND@3)") (class "Default")
      (node (ref "MEGA2560PRO1") (pin "GND@3") (pinfunction "GND_GND@3") (pintype "bidirectional"))
    )
    (net (code "162") (name "unconnected-(MEGA2560PRO1-PadA1)") (class "Default")
      (node (ref "MEGA2560PRO1") (pin "A1") (pinfunction "A1_A1") (pintype "bidirectional"))
    )
    (net (code "163") (name "unconnected-(MEGA2560PRO1-PadA3)") (class "Default")
      (node (ref "MEGA2560PRO1") (pin "A3") (pinfunction "A3_A3") (pintype "bidirectional"))
    )
    (net (code "164") (name "unconnected-(MEGA2560PRO1-PadA5)") (class "Default")
      (node (ref "MEGA2560PRO1") (pin "A5") (pinfunction "A5_A5") (pintype "bidirectional"))
    )
    (net (code "165") (name "unconnected-(MEGA2560PRO1-PadA7)") (class "Default")
      (node (ref "MEGA2560PRO1") (pin "A7") (pinfunction "A7_A7") (pintype "bidirectional"))
    )
    (net (code "166") (name "unconnected-(MEGA2560PRO1-PadA8)") (class "Default")
      (node (ref "MEGA2560PRO1") (pin "A8") (pinfunction "A8_A8") (pintype "bidirectional"))
    )
    (net (code "167") (name "unconnected-(MEGA2560PRO1-PadA9)") (class "Default")
      (node (ref "MEGA2560PRO1") (pin "A9") (pinfunction "A9_A9") (pintype "bidirectional"))
    )
    (net (code "168") (name "unconnected-(MEGA2560PRO1-PadA10)") (class "Default")
      (node (ref "MEGA2560PRO1") (pin "A10") (pinfunction "A10_A10") (pintype "bidirectional"))
    )
    (net (code "169") (name "unconnected-(MEGA2560PRO1-PadA11)") (class "Default")
      (node (ref "MEGA2560PRO1") (pin "A11") (pinfunction "A11_A11") (pintype "bidirectional"))
    )
    (net (code "170") (name "unconnected-(MEGA2560PRO1-PadA12)") (class "Default")
      (node (ref "MEGA2560PRO1") (pin "A12") (pinfunction "A12_A12") (pintype "bidirectional"))
    )
    (net (code "171") (name "unconnected-(MEGA2560PRO1-PadA13)") (class "Default")
      (node (ref "MEGA2560PRO1") (pin "A13") (pinfunction "A13_A13") (pintype "bidirectional"))
    )
    (net (code "172") (name "unconnected-(MEGA2560PRO1-PadA14)") (class "Default")
      (node (ref "MEGA2560PRO1") (pin "A14") (pinfunction "A14_A14") (pintype "bidirectional"))
    )
    (net (code "173") (name "unconnected-(MEGA2560PRO1-PadA15)") (class "Default")
      (node (ref "MEGA2560PRO1") (pin "A15") (pinfunction "A15_A15") (pintype "bidirectional"))
    )
    (net (code "174") (name "unconnected-(MEGA2560PRO1-PadAREF)") (class "Default")
      (node (ref "MEGA2560PRO1") (pin "AREF") (pinfunction "AREF_AREF") (pintype "bidirectional"))
    )
    (net (code "175") (name "unconnected-(MEGA2560PRO1-PadD6)") (class "Default")
      (node (ref "MEGA2560PRO1") (pin "D6") (pinfunction "D6_D6") (pintype "bidirectional"))
    )
    (net (code "176") (name "unconnected-(MEGA2560PRO1-PadD8)") (class "Default")
      (node (ref "MEGA2560PRO1") (pin "D8") (pinfunction "D8_D8") (pintype "bidirectional"))
    )
    (net (code "177") (name "unconnected-(MEGA2560PRO1-PadD10)") (class "Default")
      (node (ref "MEGA2560PRO1") (pin "D10") (pinfunction "D10_D10") (pintype "bidirectional"))
    )
    (net (code "178") (name "unconnected-(MEGA2560PRO1-PadMISO)") (class "Default")
      (node (ref "MEGA2560PRO1") (pin "MISO") (pinfunction "MISO_MISO") (pintype "bidirectional"))
    )
    (net (code "179") (name "unconnected-(MEGA2560PRO1-PadMOSI)") (class "Default")
      (node (ref "MEGA2560PRO1") (pin "MOSI") (pinfunction "MOSI_MOSI") (pintype "bidirectional"))
    )
    (net (code "180") (name "unconnected-(MEGA2560PRO1-PadRESET)") (class "Default")
      (node (ref "MEGA2560PRO1") (pin "RESET") (pinfunction "RESET_RESET") (pintype "bidirectional"))
    )
    (net (code "181") (name "unconnected-(MEGA2560PRO1-PadRST)") (class "Default")
      (node (ref "MEGA2560PRO1") (pin "RST") (pinfunction "RST_RST") (pintype "bidirectional"))
    )
    (net (code "182") (name "unconnected-(MEGA2560PRO1-PadRX)") (class "Default")
      (node (ref "MEGA2560PRO1") (pin "RX") (pinfunction "RX_RX") (pintype "bidirectional"))
    )
    (net (code "183") (name "unconnected-(MEGA2560PRO1-PadSCK)") (class "Default")
      (node (ref "MEGA2560PRO1") (pin "SCK") (pinfunction "SCK_SCK") (pintype "bidirectional"))
    )
    (net (code "184") (name "unconnected-(MEGA2560PRO1-PadTX)") (class "Default")
      (node (ref "MEGA2560PRO1") (pin "TX") (pinfunction "TX_TX") (pintype "bidirectional"))
    )
    (net (code "185") (name "unconnected-(U$2-GPIO0-PadC1)") (class "Default")
      (node (ref "U$2") (pin "C1") (pinfunction "GPIO0_C1") (pintype "bidirectional"))
    )
    (net (code "186") (name "unconnected-(U$2-GPIO2-PadB1)") (class "Default")
      (node (ref "U$2") (pin "B1") (pinfunction "GPIO2_B1") (pintype "bidirectional"))
    )
    (net (code "187") (name "unconnected-(U$4-RST-Pad7)") (class "Default")
      (node (ref "U$4") (pin "7") (pinfunction "RST_7") (pintype "bidirectional"))
    )
  )
)
